# led-analog.net
KiCad netlist of a schematic drawn in EAGLE
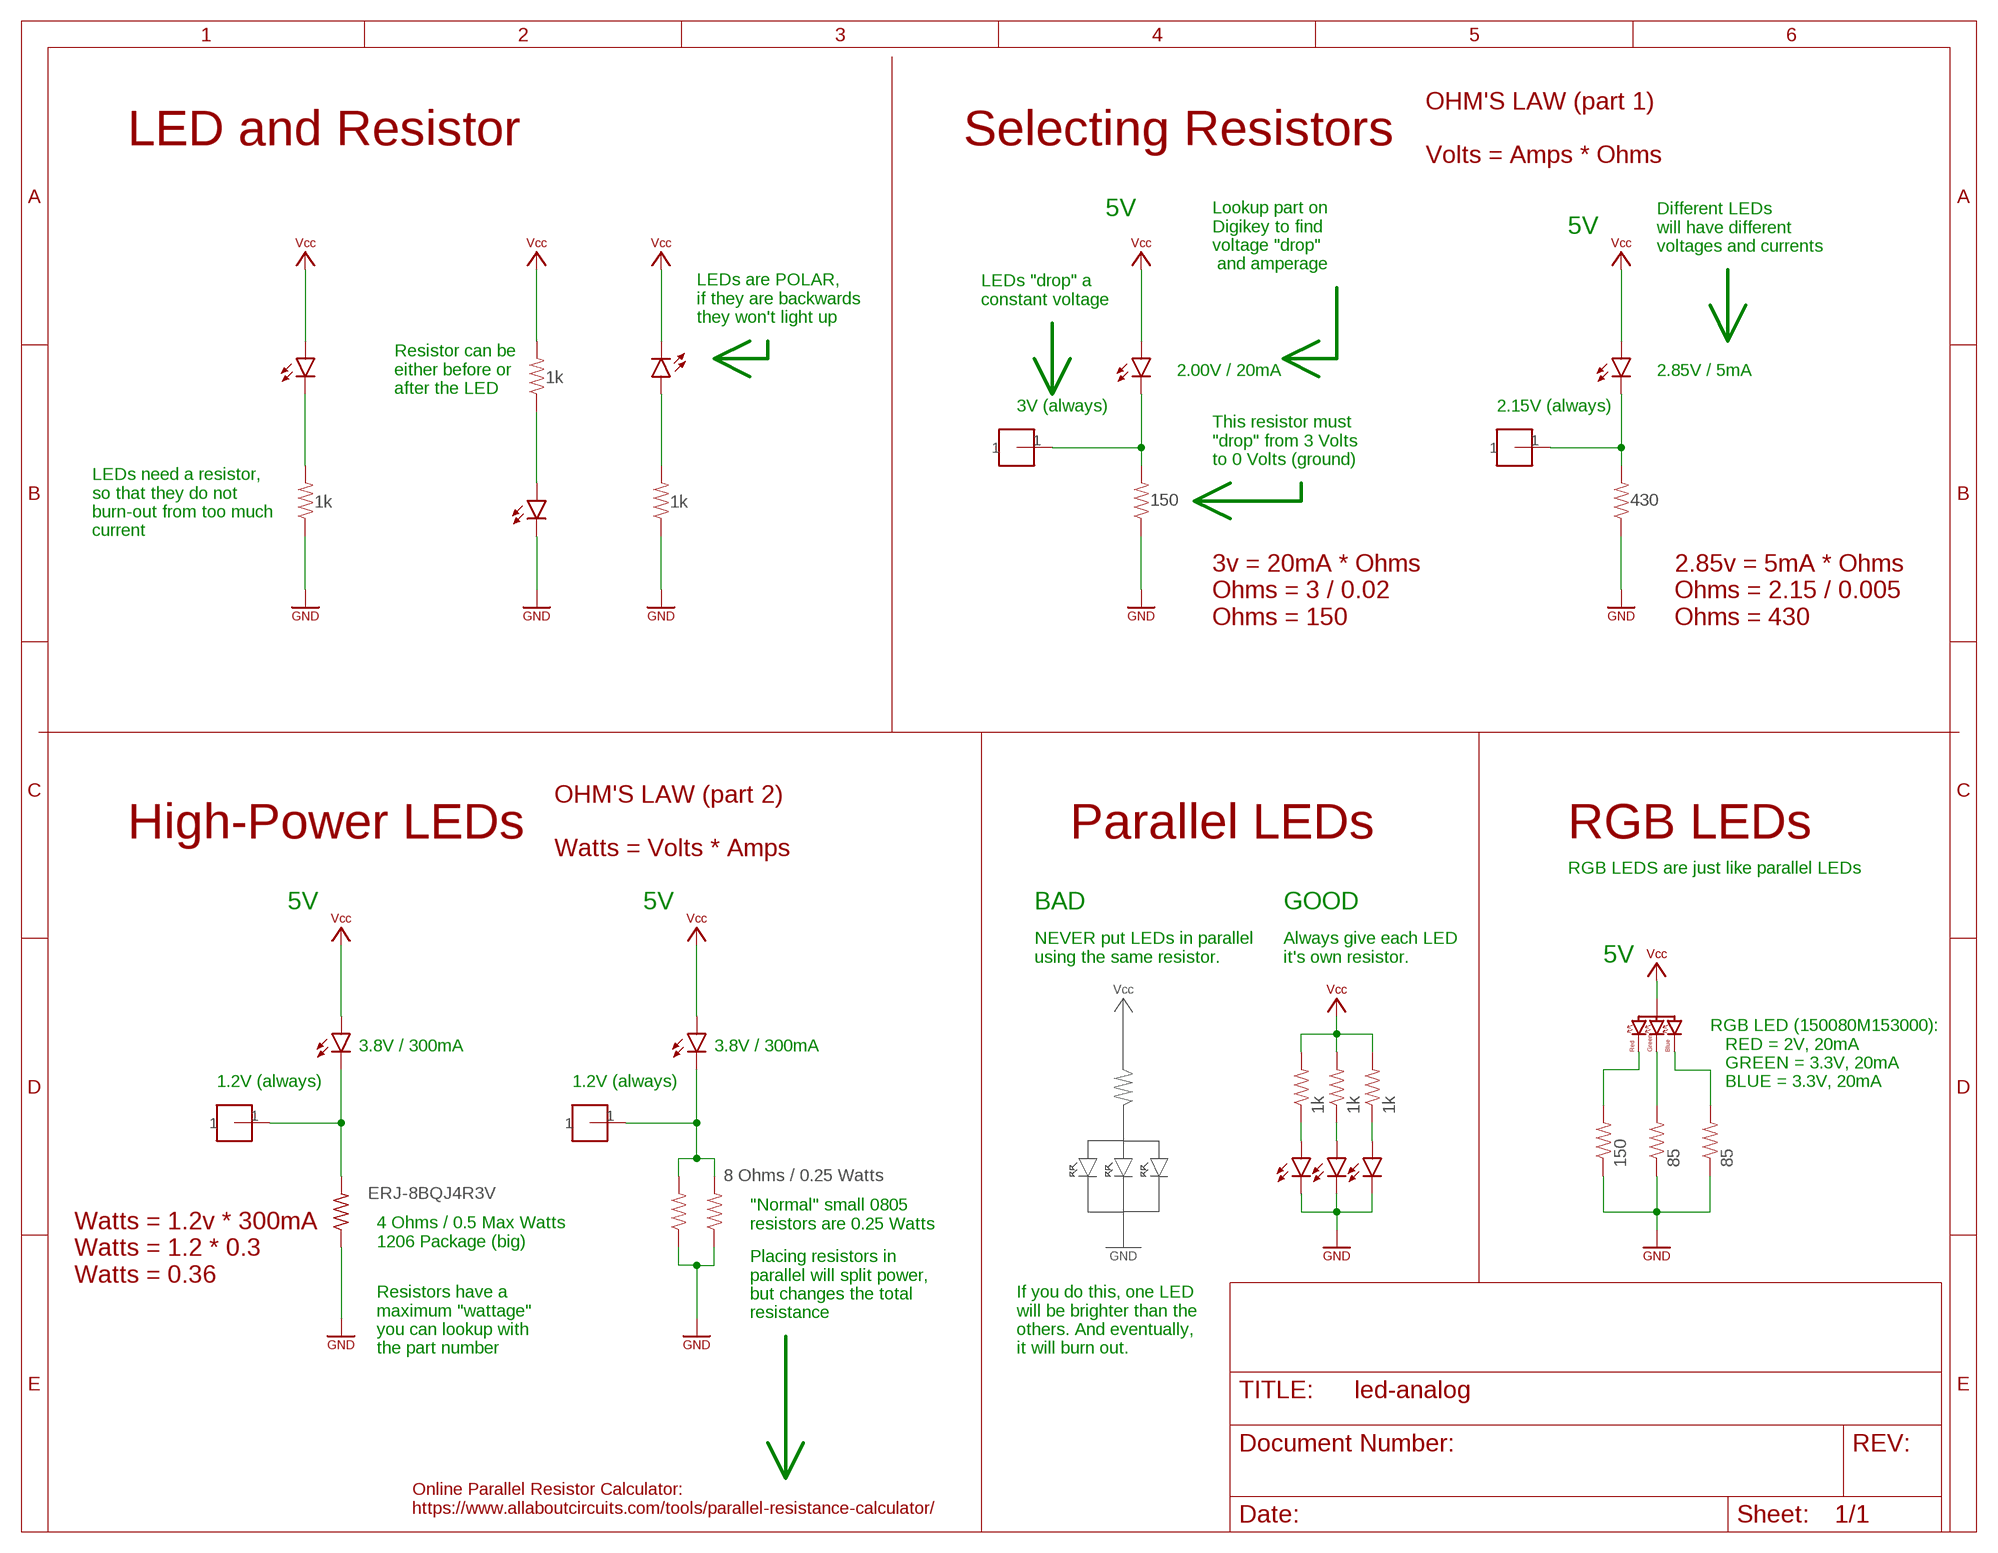
[diagram p0: schematic, sheet 1]

(export (version "E")
  (design (tool "Eeschema 10.0.6"))
  (components
    (comp (ref "LED3")
      (value "LED-0805")
      (footprint "eagle-import:CHIP-LED0805")
      (libsource (lib "eagle-import") (part "LED-0805"))
    )
    (comp (ref "LED4")
      (value "LED-0805")
      (footprint "eagle-import:CHIP-LED0805")
      (libsource (lib "eagle-import") (part "LED-0805"))
    )
    (comp (ref "LED5")
      (value "LED-0805")
      (footprint "eagle-import:CHIP-LED0805")
      (libsource (lib "eagle-import") (part "LED-0805"))
    )
    (comp (ref "LED6")
      (value "LED-0805")
      (footprint "eagle-import:CHIP-LED0805")
      (libsource (lib "eagle-import") (part "LED-0805"))
    )
    (comp (ref "LED7")
      (value "LED-0805")
      (footprint "eagle-import:CHIP-LED0805")
      (libsource (lib "eagle-import") (part "LED-0805"))
    )
    (comp (ref "LED8")
      (value "LED-0805")
      (footprint "eagle-import:CHIP-LED0805")
      (libsource (lib "eagle-import") (part "LED-0805"))
    )
    (comp (ref "LED9")
      (value "LED-0805")
      (footprint "eagle-import:CHIP-LED0805")
      (libsource (lib "eagle-import") (part "LED-0805"))
    )
    (comp (ref "LED10")
      (value "LED-0805")
      (footprint "eagle-import:CHIP-LED0805")
      (libsource (lib "eagle-import") (part "LED-0805"))
    )
    (comp (ref "LED11")
      (value "LED-0805")
      (footprint "eagle-import:CHIP-LED0805")
      (libsource (lib "eagle-import") (part "LED-0805"))
    )
    (comp (ref "LED12")
      (value "LED-0805")
      (footprint "eagle-import:CHIP-LED0805")
      (libsource (lib "eagle-import") (part "LED-0805"))
    )
    (comp (ref "R3")
      (value "1k")
      (footprint "eagle-import:0805")
      (libsource (lib "eagle-import") (part "COMPONENT_RESISTOR-0805"))
    )
    (comp (ref "R4")
      (value "1k")
      (footprint "eagle-import:0805")
      (libsource (lib "eagle-import") (part "COMPONENT_RESISTOR-0805"))
    )
    (comp (ref "R5")
      (value "1k")
      (footprint "eagle-import:0805")
      (libsource (lib "eagle-import") (part "COMPONENT_RESISTOR-0805"))
    )
    (comp (ref "R6")
      (value "150")
      (footprint "eagle-import:0805")
      (libsource (lib "eagle-import") (part "COMPONENT_RESISTOR-0805"))
    )
    (comp (ref "R7")
      (value "85")
      (footprint "eagle-import:0805")
      (libsource (lib "eagle-import") (part "COMPONENT_RESISTOR-0805"))
    )
    (comp (ref "R8")
      (value "85")
      (footprint "eagle-import:0805")
      (libsource (lib "eagle-import") (part "COMPONENT_RESISTOR-0805"))
    )
    (comp (ref "R9")
      (value "1k")
      (footprint "eagle-import:0805")
      (libsource (lib "eagle-import") (part "COMPONENT_RESISTOR-0805"))
    )
    (comp (ref "R10")
      (value "1k")
      (footprint "eagle-import:0805")
      (libsource (lib "eagle-import") (part "COMPONENT_RESISTOR-0805"))
    )
    (comp (ref "R11")
      (value "1k")
      (footprint "eagle-import:0805")
      (libsource (lib "eagle-import") (part "COMPONENT_RESISTOR-0805"))
    )
    (comp (ref "R12")
      (value "430")
      (footprint "eagle-import:0805")
      (libsource (lib "eagle-import") (part "COMPONENT_RESISTOR-0805"))
    )
    (comp (ref "R13")
      (value "8 Ohms / 0.25 Watts")
      (footprint "eagle-import:0805")
      (libsource (lib "eagle-import") (part "COMPONENT_RESISTOR-0805"))
    )
    (comp (ref "R14")
      (value "ERJ-8BQJ4R3V")
      (footprint "eagle-import:R1206")
      (libsource (lib "eagle-import") (part "R-US_R1206"))
    )
    (comp (ref "R15")
      (value "150")
      (footprint "eagle-import:0805")
      (libsource (lib "eagle-import") (part "COMPONENT_RESISTOR-0805"))
    )
    (comp (ref "R16")
      (value "8 Ohms / 0.25 Watts")
      (footprint "eagle-import:0805")
      (libsource (lib "eagle-import") (part "COMPONENT_RESISTOR-0805"))
    )
    (comp (ref "U$1")
      (value "150080M153000")
      (footprint "eagle-import:150080M153000")
      (libsource (lib "eagle-import") (part "LED_RGB"))
    )
    (comp (ref "U$2")
      (value "HEADER-1-TESTPOINT")
      (footprint "eagle-import:TESTPOINT-1")
      (libsource (lib "eagle-import") (part "HEADER-1-TESTPOINT"))
    )
    (comp (ref "U$3")
      (value "HEADER-1-TESTPOINT")
      (footprint "eagle-import:TESTPOINT-1")
      (libsource (lib "eagle-import") (part "HEADER-1-TESTPOINT"))
    )
    (comp (ref "U$4")
      (value "HEADER-1-TESTPOINT")
      (footprint "eagle-import:TESTPOINT-1")
      (libsource (lib "eagle-import") (part "HEADER-1-TESTPOINT"))
    )
    (comp (ref "U$5")
      (value "HEADER-1-TESTPOINT")
      (footprint "eagle-import:TESTPOINT-1")
      (libsource (lib "eagle-import") (part "HEADER-1-TESTPOINT"))
    )
  )
  (nets
    (net (code "2") (name "Net-(LED3-PadA)") (class "Default")
      (node (ref "LED3") (pin "A") (pinfunction "A_A") (pintype "passive"))
      (node (ref "R3") (pin "1") (pinfunction "1_1") (pintype "passive"))
    )
    (net (code "3") (name "Net-(LED4-PadA)") (class "Default")
      (node (ref "LED4") (pin "A") (pinfunction "A_A") (pintype "passive"))
      (node (ref "R4") (pin "1") (pinfunction "1_1") (pintype "passive"))
    )
    (net (code "4") (name "Net-(LED5-PadA)") (class "Default")
      (node (ref "LED5") (pin "A") (pinfunction "A_A") (pintype "passive"))
      (node (ref "R5") (pin "1") (pinfunction "1_1") (pintype "passive"))
    )
    (net (code "5") (name "Net-(LED6-PadC)") (class "Default")
      (node (ref "LED6") (pin "C") (pinfunction "C_C") (pintype "passive"))
      (node (ref "R9") (pin "2") (pinfunction "2_2") (pintype "passive"))
    )
    (net (code "6") (name "Net-(LED7-PadA)") (class "Default")
      (node (ref "LED7") (pin "A") (pinfunction "A_A") (pintype "passive"))
      (node (ref "R10") (pin "1") (pinfunction "1_1") (pintype "passive"))
    )
    (net (code "7") (name "Net-(LED8-PadA)") (class "Default")
      (node (ref "LED8") (pin "A") (pinfunction "A_A") (pintype "passive"))
      (node (ref "R11") (pin "2") (pinfunction "2_2") (pintype "passive"))
    )
    (net (code "8") (name "Net-(LED9-PadC)") (class "Default")
      (node (ref "LED9") (pin "C") (pinfunction "C_C") (pintype "passive"))
      (node (ref "R15") (pin "2") (pinfunction "2_2") (pintype "passive"))
      (node (ref "U$5") (pin "1") (pinfunction "1_1") (pintype "bidirectional"))
    )
    (net (code "9") (name "Net-(LED10-PadC)") (class "Default")
      (node (ref "LED10") (pin "C") (pinfunction "C_C") (pintype "passive"))
      (node (ref "R12") (pin "2") (pinfunction "2_2") (pintype "passive"))
      (node (ref "U$4") (pin "1") (pinfunction "1_1") (pintype "bidirectional"))
    )
    (net (code "10") (name "Net-(LED11-PadC)") (class "Default")
      (node (ref "LED11") (pin "C") (pinfunction "C_C") (pintype "passive"))
      (node (ref "R14") (pin "2") (pinfunction "2_2") (pintype "passive"))
      (node (ref "U$2") (pin "1") (pinfunction "1_1") (pintype "bidirectional"))
    )
    (net (code "11") (name "Net-(LED12-PadC)") (class "Default")
      (node (ref "LED12") (pin "C") (pinfunction "C_C") (pintype "passive"))
      (node (ref "R13") (pin "2") (pinfunction "2_2") (pintype "passive"))
      (node (ref "R16") (pin "2") (pinfunction "2_2") (pintype "passive"))
      (node (ref "U$3") (pin "1") (pinfunction "1_1") (pintype "bidirectional"))
    )
    (net (code "12") (name "Net-(U$1-BLUE)") (class "Default")
      (node (ref "R8") (pin "2") (pinfunction "2_2") (pintype "passive"))
      (node (ref "U$1") (pin "3") (pinfunction "BLUE_3") (pintype "bidirectional"))
    )
    (net (code "13") (name "Net-(U$1-GREEN)") (class "Default")
      (node (ref "R7") (pin "2") (pinfunction "2_2") (pintype "passive"))
      (node (ref "U$1") (pin "2") (pinfunction "GREEN_2") (pintype "bidirectional"))
    )
    (net (code "14") (name "Net-(U$1-RED)") (class "Default")
      (node (ref "R6") (pin "2") (pinfunction "2_2") (pintype "passive"))
      (node (ref "U$1") (pin "1") (pinfunction "RED_1") (pintype "bidirectional"))
    )
    (net (code "15") (name "SYMBOL_GND") (class "Default")
      (node (ref "LED3") (pin "C") (pinfunction "C_C") (pintype "passive"))
      (node (ref "LED4") (pin "C") (pinfunction "C_C") (pintype "passive"))
      (node (ref "LED5") (pin "C") (pinfunction "C_C") (pintype "passive"))
      (node (ref "LED7") (pin "C") (pinfunction "C_C") (pintype "passive"))
      (node (ref "R11") (pin "1") (pinfunction "1_1") (pintype "passive"))
      (node (ref "R12") (pin "1") (pinfunction "1_1") (pintype "passive"))
      (node (ref "R13") (pin "1") (pinfunction "1_1") (pintype "passive"))
      (node (ref "R14") (pin "1") (pinfunction "1_1") (pintype "passive"))
      (node (ref "R15") (pin "1") (pinfunction "1_1") (pintype "passive"))
      (node (ref "R16") (pin "1") (pinfunction "1_1") (pintype "passive"))
      (node (ref "R6") (pin "1") (pinfunction "1_1") (pintype "passive"))
      (node (ref "R7") (pin "1") (pinfunction "1_1") (pintype "passive"))
      (node (ref "R8") (pin "1") (pinfunction "1_1") (pintype "passive"))
      (node (ref "R9") (pin "1") (pinfunction "1_1") (pintype "passive"))
    )
    (net (code "16") (name "SYMBOL_VCC") (class "Default")
      (node (ref "LED10") (pin "A") (pinfunction "A_A") (pintype "passive"))
      (node (ref "LED11") (pin "A") (pinfunction "A_A") (pintype "passive"))
      (node (ref "LED12") (pin "A") (pinfunction "A_A") (pintype "passive"))
      (node (ref "LED6") (pin "A") (pinfunction "A_A") (pintype "passive"))
      (node (ref "LED8") (pin "C") (pinfunction "C_C") (pintype "passive"))
      (node (ref "LED9") (pin "A") (pinfunction "A_A") (pintype "passive"))
      (node (ref "R10") (pin "2") (pinfunction "2_2") (pintype "passive"))
      (node (ref "R3") (pin "2") (pinfunction "2_2") (pintype "passive"))
      (node (ref "R4") (pin "2") (pinfunction "2_2") (pintype "passive"))
      (node (ref "R5") (pin "2") (pinfunction "2_2") (pintype "passive"))
      (node (ref "U$1") (pin "4") (pinfunction "ANODE_4") (pintype "bidirectional"))
    )
  )
)
